# 2_dsub_to_pins.net
KiCad netlist of a schematic drawn in EAGLE
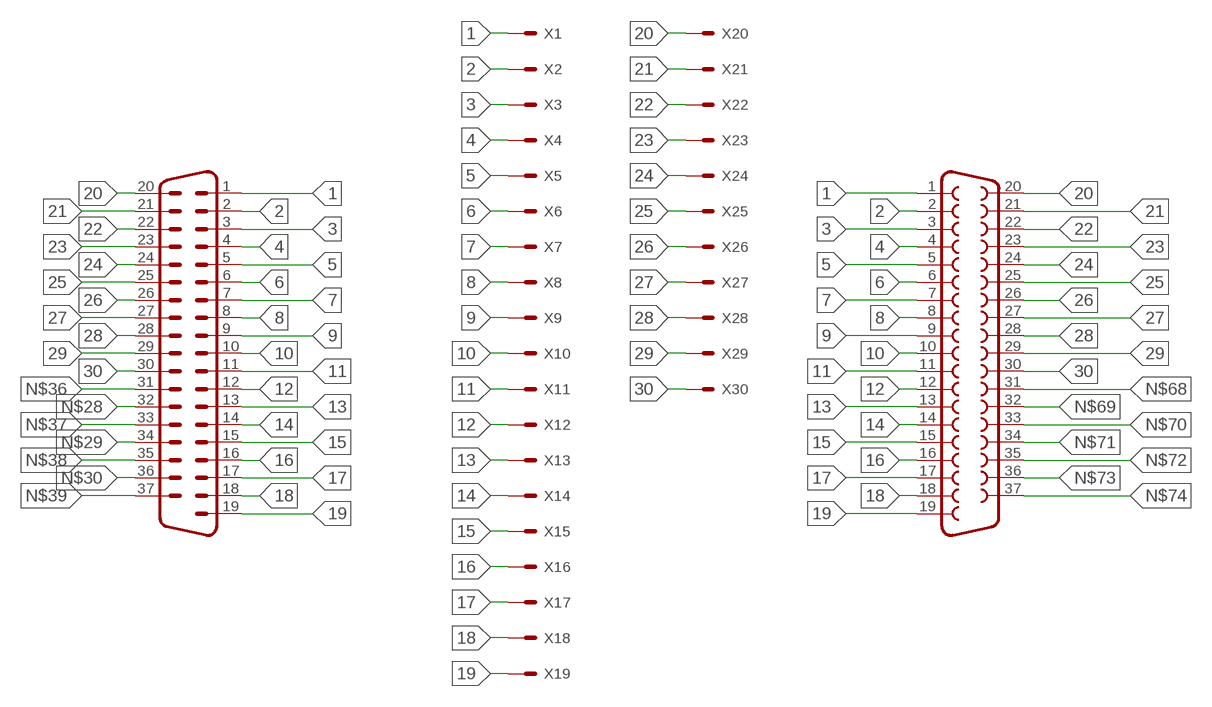
[diagram p0: schematic, sheet 1]

(export (version "E")
  (design (tool "Eeschema 10.0.6"))
  (components
    (comp (ref "X1")
      (value "22-23-2021")
      (footprint "eagle-import:22-23-2021")
      (fields (field (name "MF") "MOLEX"))
      (libsource (lib "eagle-import") (part "22-23-2021"))
    )
    (comp (ref "X2")
      (value "22-23-2021")
      (footprint "eagle-import:22-23-2021")
      (fields (field (name "MF") "MOLEX"))
      (libsource (lib "eagle-import") (part "22-23-2021"))
    )
    (comp (ref "X3")
      (value "22-23-2021")
      (footprint "eagle-import:22-23-2021")
      (fields (field (name "MF") "MOLEX"))
      (libsource (lib "eagle-import") (part "22-23-2021"))
    )
    (comp (ref "X4")
      (value "22-23-2021")
      (footprint "eagle-import:22-23-2021")
      (fields (field (name "MF") "MOLEX"))
      (libsource (lib "eagle-import") (part "22-23-2021"))
    )
    (comp (ref "X5")
      (value "22-23-2021")
      (footprint "eagle-import:22-23-2021")
      (fields (field (name "MF") "MOLEX"))
      (libsource (lib "eagle-import") (part "22-23-2021"))
    )
    (comp (ref "X6")
      (value "22-23-2021")
      (footprint "eagle-import:22-23-2021")
      (fields (field (name "MF") "MOLEX"))
      (libsource (lib "eagle-import") (part "22-23-2021"))
    )
    (comp (ref "X7")
      (value "22-23-2021")
      (footprint "eagle-import:22-23-2021")
      (fields (field (name "MF") "MOLEX"))
      (libsource (lib "eagle-import") (part "22-23-2021"))
    )
    (comp (ref "X8")
      (value "22-23-2021")
      (footprint "eagle-import:22-23-2021")
      (fields (field (name "MF") "MOLEX"))
      (libsource (lib "eagle-import") (part "22-23-2021"))
    )
    (comp (ref "X9")
      (value "22-23-2021")
      (footprint "eagle-import:22-23-2021")
      (fields (field (name "MF") "MOLEX"))
      (libsource (lib "eagle-import") (part "22-23-2021"))
    )
    (comp (ref "X10")
      (value "22-23-2021")
      (footprint "eagle-import:22-23-2021")
      (fields (field (name "MF") "MOLEX"))
      (libsource (lib "eagle-import") (part "22-23-2021"))
    )
    (comp (ref "X11")
      (value "22-23-2021")
      (footprint "eagle-import:22-23-2021")
      (fields (field (name "MF") "MOLEX"))
      (libsource (lib "eagle-import") (part "22-23-2021"))
    )
    (comp (ref "X12")
      (value "22-23-2021")
      (footprint "eagle-import:22-23-2021")
      (fields (field (name "MF") "MOLEX"))
      (libsource (lib "eagle-import") (part "22-23-2021"))
    )
    (comp (ref "X13")
      (value "22-23-2021")
      (footprint "eagle-import:22-23-2021")
      (fields (field (name "MF") "MOLEX"))
      (libsource (lib "eagle-import") (part "22-23-2021"))
    )
    (comp (ref "X14")
      (value "22-23-2021")
      (footprint "eagle-import:22-23-2021")
      (fields (field (name "MF") "MOLEX"))
      (libsource (lib "eagle-import") (part "22-23-2021"))
    )
    (comp (ref "X15")
      (value "22-23-2021")
      (footprint "eagle-import:22-23-2021")
      (fields (field (name "MF") "MOLEX"))
      (libsource (lib "eagle-import") (part "22-23-2021"))
    )
    (comp (ref "X16")
      (value "22-23-2021")
      (footprint "eagle-import:22-23-2021")
      (fields (field (name "MF") "MOLEX"))
      (libsource (lib "eagle-import") (part "22-23-2021"))
    )
    (comp (ref "X17")
      (value "22-23-2021")
      (footprint "eagle-import:22-23-2021")
      (fields (field (name "MF") "MOLEX"))
      (libsource (lib "eagle-import") (part "22-23-2021"))
    )
    (comp (ref "X18")
      (value "22-23-2021")
      (footprint "eagle-import:22-23-2021")
      (fields (field (name "MF") "MOLEX"))
      (libsource (lib "eagle-import") (part "22-23-2021"))
    )
    (comp (ref "X19")
      (value "22-23-2021")
      (footprint "eagle-import:22-23-2021")
      (fields (field (name "MF") "MOLEX"))
      (libsource (lib "eagle-import") (part "22-23-2021"))
    )
    (comp (ref "X20")
      (value "22-23-2021")
      (footprint "eagle-import:22-23-2021")
      (fields (field (name "MF") "MOLEX"))
      (libsource (lib "eagle-import") (part "22-23-2021"))
    )
    (comp (ref "X21")
      (value "22-23-2021")
      (footprint "eagle-import:22-23-2021")
      (fields (field (name "MF") "MOLEX"))
      (libsource (lib "eagle-import") (part "22-23-2021"))
    )
    (comp (ref "X22")
      (value "22-23-2021")
      (footprint "eagle-import:22-23-2021")
      (fields (field (name "MF") "MOLEX"))
      (libsource (lib "eagle-import") (part "22-23-2021"))
    )
    (comp (ref "X23")
      (value "22-23-2021")
      (footprint "eagle-import:22-23-2021")
      (fields (field (name "MF") "MOLEX"))
      (libsource (lib "eagle-import") (part "22-23-2021"))
    )
    (comp (ref "X24")
      (value "22-23-2021")
      (footprint "eagle-import:22-23-2021")
      (fields (field (name "MF") "MOLEX"))
      (libsource (lib "eagle-import") (part "22-23-2021"))
    )
    (comp (ref "X25")
      (value "22-23-2021")
      (footprint "eagle-import:22-23-2021")
      (fields (field (name "MF") "MOLEX"))
      (libsource (lib "eagle-import") (part "22-23-2021"))
    )
    (comp (ref "X26")
      (value "22-23-2021")
      (footprint "eagle-import:22-23-2021")
      (fields (field (name "MF") "MOLEX"))
      (libsource (lib "eagle-import") (part "22-23-2021"))
    )
    (comp (ref "X27")
      (value "22-23-2021")
      (footprint "eagle-import:22-23-2021")
      (fields (field (name "MF") "MOLEX"))
      (libsource (lib "eagle-import") (part "22-23-2021"))
    )
    (comp (ref "X28")
      (value "22-23-2021")
      (footprint "eagle-import:22-23-2021")
      (fields (field (name "MF") "MOLEX"))
      (libsource (lib "eagle-import") (part "22-23-2021"))
    )
    (comp (ref "X29")
      (value "22-23-2021")
      (footprint "eagle-import:22-23-2021")
      (fields (field (name "MF") "MOLEX"))
      (libsource (lib "eagle-import") (part "22-23-2021"))
    )
    (comp (ref "X30")
      (value "22-23-2021")
      (footprint "eagle-import:22-23-2021")
      (fields (field (name "MF") "MOLEX"))
      (libsource (lib "eagle-import") (part "22-23-2021"))
    )
    (comp (ref "X33")
      (value "M37HP")
      (footprint "eagle-import:M37HP")
      (libsource (lib "eagle-import") (part "M37HP"))
    )
    (comp (ref "X34")
      (value "F37HP")
      (footprint "eagle-import:F37HP")
      (libsource (lib "eagle-import") (part "F37HP"))
    )
  )
  (nets
    (net (code "1") (name "1") (class "Default")
      (node (ref "X1") (pin "1") (pinfunction "S_1") (pintype "passive"))
      (node (ref "X33") (pin "1") (pinfunction "1_1") (pintype "passive"))
      (node (ref "X34") (pin "1") (pinfunction "1_1") (pintype "passive"))
    )
    (net (code "2") (name "2") (class "Default")
      (node (ref "X2") (pin "1") (pinfunction "S_1") (pintype "passive"))
      (node (ref "X33") (pin "2") (pinfunction "2_2") (pintype "passive"))
      (node (ref "X34") (pin "2") (pinfunction "2_2") (pintype "passive"))
    )
    (net (code "3") (name "3") (class "Default")
      (node (ref "X3") (pin "1") (pinfunction "S_1") (pintype "passive"))
      (node (ref "X33") (pin "3") (pinfunction "3_3") (pintype "passive"))
      (node (ref "X34") (pin "3") (pinfunction "3_3") (pintype "passive"))
    )
    (net (code "4") (name "4") (class "Default")
      (node (ref "X33") (pin "4") (pinfunction "4_4") (pintype "passive"))
      (node (ref "X34") (pin "4") (pinfunction "4_4") (pintype "passive"))
      (node (ref "X4") (pin "1") (pinfunction "S_1") (pintype "passive"))
    )
    (net (code "5") (name "5") (class "Default")
      (node (ref "X33") (pin "5") (pinfunction "5_5") (pintype "passive"))
      (node (ref "X34") (pin "5") (pinfunction "5_5") (pintype "passive"))
      (node (ref "X5") (pin "1") (pinfunction "S_1") (pintype "passive"))
    )
    (net (code "6") (name "6") (class "Default")
      (node (ref "X33") (pin "6") (pinfunction "6_6") (pintype "passive"))
      (node (ref "X34") (pin "6") (pinfunction "6_6") (pintype "passive"))
      (node (ref "X6") (pin "1") (pinfunction "S_1") (pintype "passive"))
    )
    (net (code "7") (name "7") (class "Default")
      (node (ref "X33") (pin "7") (pinfunction "7_7") (pintype "passive"))
      (node (ref "X34") (pin "7") (pinfunction "7_7") (pintype "passive"))
      (node (ref "X7") (pin "1") (pinfunction "S_1") (pintype "passive"))
    )
    (net (code "8") (name "8") (class "Default")
      (node (ref "X33") (pin "8") (pinfunction "8_8") (pintype "passive"))
      (node (ref "X34") (pin "8") (pinfunction "8_8") (pintype "passive"))
      (node (ref "X8") (pin "1") (pinfunction "S_1") (pintype "passive"))
    )
    (net (code "9") (name "9") (class "Default")
      (node (ref "X33") (pin "9") (pinfunction "9_9") (pintype "passive"))
      (node (ref "X34") (pin "9") (pinfunction "9_9") (pintype "passive"))
      (node (ref "X9") (pin "1") (pinfunction "S_1") (pintype "passive"))
    )
    (net (code "10") (name "10") (class "Default")
      (node (ref "X10") (pin "1") (pinfunction "S_1") (pintype "passive"))
      (node (ref "X33") (pin "10") (pinfunction "10_10") (pintype "passive"))
      (node (ref "X34") (pin "10") (pinfunction "10_10") (pintype "passive"))
    )
    (net (code "11") (name "11") (class "Default")
      (node (ref "X11") (pin "1") (pinfunction "S_1") (pintype "passive"))
      (node (ref "X33") (pin "11") (pinfunction "11_11") (pintype "passive"))
      (node (ref "X34") (pin "11") (pinfunction "11_11") (pintype "passive"))
    )
    (net (code "12") (name "12") (class "Default")
      (node (ref "X12") (pin "1") (pinfunction "S_1") (pintype "passive"))
      (node (ref "X33") (pin "12") (pinfunction "12_12") (pintype "passive"))
      (node (ref "X34") (pin "12") (pinfunction "12_12") (pintype "passive"))
    )
    (net (code "13") (name "13") (class "Default")
      (node (ref "X13") (pin "1") (pinfunction "S_1") (pintype "passive"))
      (node (ref "X33") (pin "13") (pinfunction "13_13") (pintype "passive"))
      (node (ref "X34") (pin "13") (pinfunction "13_13") (pintype "passive"))
    )
    (net (code "14") (name "14") (class "Default")
      (node (ref "X14") (pin "1") (pinfunction "S_1") (pintype "passive"))
      (node (ref "X33") (pin "14") (pinfunction "14_14") (pintype "passive"))
      (node (ref "X34") (pin "14") (pinfunction "14_14") (pintype "passive"))
    )
    (net (code "15") (name "15") (class "Default")
      (node (ref "X15") (pin "1") (pinfunction "S_1") (pintype "passive"))
      (node (ref "X33") (pin "15") (pinfunction "15_15") (pintype "passive"))
      (node (ref "X34") (pin "15") (pinfunction "15_15") (pintype "passive"))
    )
    (net (code "16") (name "16") (class "Default")
      (node (ref "X16") (pin "1") (pinfunction "S_1") (pintype "passive"))
      (node (ref "X33") (pin "16") (pinfunction "16_16") (pintype "passive"))
      (node (ref "X34") (pin "16") (pinfunction "16_16") (pintype "passive"))
    )
    (net (code "17") (name "17") (class "Default")
      (node (ref "X17") (pin "1") (pinfunction "S_1") (pintype "passive"))
      (node (ref "X33") (pin "17") (pinfunction "17_17") (pintype "passive"))
      (node (ref "X34") (pin "17") (pinfunction "17_17") (pintype "passive"))
    )
    (net (code "18") (name "18") (class "Default")
      (node (ref "X18") (pin "1") (pinfunction "S_1") (pintype "passive"))
      (node (ref "X33") (pin "18") (pinfunction "18_18") (pintype "passive"))
      (node (ref "X34") (pin "18") (pinfunction "18_18") (pintype "passive"))
    )
    (net (code "19") (name "19") (class "Default")
      (node (ref "X19") (pin "1") (pinfunction "S_1") (pintype "passive"))
      (node (ref "X33") (pin "19") (pinfunction "19_19") (pintype "passive"))
      (node (ref "X34") (pin "19") (pinfunction "19_19") (pintype "passive"))
    )
    (net (code "20") (name "20") (class "Default")
      (node (ref "X20") (pin "1") (pinfunction "S_1") (pintype "passive"))
      (node (ref "X33") (pin "20") (pinfunction "20_20") (pintype "passive"))
      (node (ref "X34") (pin "20") (pinfunction "20_20") (pintype "passive"))
    )
    (net (code "21") (name "21") (class "Default")
      (node (ref "X21") (pin "1") (pinfunction "S_1") (pintype "passive"))
      (node (ref "X33") (pin "21") (pinfunction "21_21") (pintype "passive"))
      (node (ref "X34") (pin "21") (pinfunction "21_21") (pintype "passive"))
    )
    (net (code "22") (name "22") (class "Default")
      (node (ref "X22") (pin "1") (pinfunction "S_1") (pintype "passive"))
      (node (ref "X33") (pin "22") (pinfunction "22_22") (pintype "passive"))
      (node (ref "X34") (pin "22") (pinfunction "22_22") (pintype "passive"))
    )
    (net (code "23") (name "23") (class "Default")
      (node (ref "X23") (pin "1") (pinfunction "S_1") (pintype "passive"))
      (node (ref "X33") (pin "23") (pinfunction "23_23") (pintype "passive"))
      (node (ref "X34") (pin "23") (pinfunction "23_23") (pintype "passive"))
    )
    (net (code "24") (name "24") (class "Default")
      (node (ref "X24") (pin "1") (pinfunction "S_1") (pintype "passive"))
      (node (ref "X33") (pin "24") (pinfunction "24_24") (pintype "passive"))
      (node (ref "X34") (pin "24") (pinfunction "24_24") (pintype "passive"))
    )
    (net (code "25") (name "25") (class "Default")
      (node (ref "X25") (pin "1") (pinfunction "S_1") (pintype "passive"))
      (node (ref "X33") (pin "25") (pinfunction "25_25") (pintype "passive"))
      (node (ref "X34") (pin "25") (pinfunction "25_25") (pintype "passive"))
    )
    (net (code "26") (name "26") (class "Default")
      (node (ref "X26") (pin "1") (pinfunction "S_1") (pintype "passive"))
      (node (ref "X33") (pin "26") (pinfunction "26_26") (pintype "passive"))
      (node (ref "X34") (pin "26") (pinfunction "26_26") (pintype "passive"))
    )
    (net (code "27") (name "27") (class "Default")
      (node (ref "X27") (pin "1") (pinfunction "S_1") (pintype "passive"))
      (node (ref "X33") (pin "27") (pinfunction "27_27") (pintype "passive"))
      (node (ref "X34") (pin "27") (pinfunction "27_27") (pintype "passive"))
    )
    (net (code "28") (name "28") (class "Default")
      (node (ref "X28") (pin "1") (pinfunction "S_1") (pintype "passive"))
      (node (ref "X33") (pin "28") (pinfunction "28_28") (pintype "passive"))
      (node (ref "X34") (pin "28") (pinfunction "28_28") (pintype "passive"))
    )
    (net (code "29") (name "29") (class "Default")
      (node (ref "X29") (pin "1") (pinfunction "S_1") (pintype "passive"))
      (node (ref "X33") (pin "29") (pinfunction "29_29") (pintype "passive"))
      (node (ref "X34") (pin "29") (pinfunction "29_29") (pintype "passive"))
    )
    (net (code "30") (name "30") (class "Default")
      (node (ref "X30") (pin "1") (pinfunction "S_1") (pintype "passive"))
      (node (ref "X33") (pin "30") (pinfunction "30_30") (pintype "passive"))
      (node (ref "X34") (pin "30") (pinfunction "30_30") (pintype "passive"))
    )
    (net (code "31") (name "N$28") (class "Default")
      (node (ref "X33") (pin "32") (pinfunction "32_32") (pintype "passive"))
    )
    (net (code "32") (name "N$29") (class "Default")
      (node (ref "X33") (pin "34") (pinfunction "34_34") (pintype "passive"))
    )
    (net (code "33") (name "N$30") (class "Default")
      (node (ref "X33") (pin "36") (pinfunction "36_36") (pintype "passive"))
    )
    (net (code "34") (name "N$36") (class "Default")
      (node (ref "X33") (pin "31") (pinfunction "31_31") (pintype "passive"))
    )
    (net (code "35") (name "N$37") (class "Default")
      (node (ref "X33") (pin "33") (pinfunction "33_33") (pintype "passive"))
    )
    (net (code "36") (name "N$38") (class "Default")
      (node (ref "X33") (pin "35") (pinfunction "35_35") (pintype "passive"))
    )
    (net (code "37") (name "N$39") (class "Default")
      (node (ref "X33") (pin "37") (pinfunction "37_37") (pintype "passive"))
    )
    (net (code "38") (name "N$68") (class "Default")
      (node (ref "X34") (pin "31") (pinfunction "31_31") (pintype "passive"))
    )
    (net (code "39") (name "N$69") (class "Default")
      (node (ref "X34") (pin "32") (pinfunction "32_32") (pintype "passive"))
    )
    (net (code "40") (name "N$70") (class "Default")
      (node (ref "X34") (pin "33") (pinfunction "33_33") (pintype "passive"))
    )
    (net (code "41") (name "N$71") (class "Default")
      (node (ref "X34") (pin "34") (pinfunction "34_34") (pintype "passive"))
    )
    (net (code "42") (name "N$72") (class "Default")
      (node (ref "X34") (pin "35") (pinfunction "35_35") (pintype "passive"))
    )
    (net (code "43") (name "N$73") (class "Default")
      (node (ref "X34") (pin "36") (pinfunction "36_36") (pintype "passive"))
    )
    (net (code "44") (name "N$74") (class "Default")
      (node (ref "X34") (pin "37") (pinfunction "37_37") (pintype "passive"))
    )
  )
)
